# Sheet1.net
KiCad netlist of a schematic drawn in Altium Designer
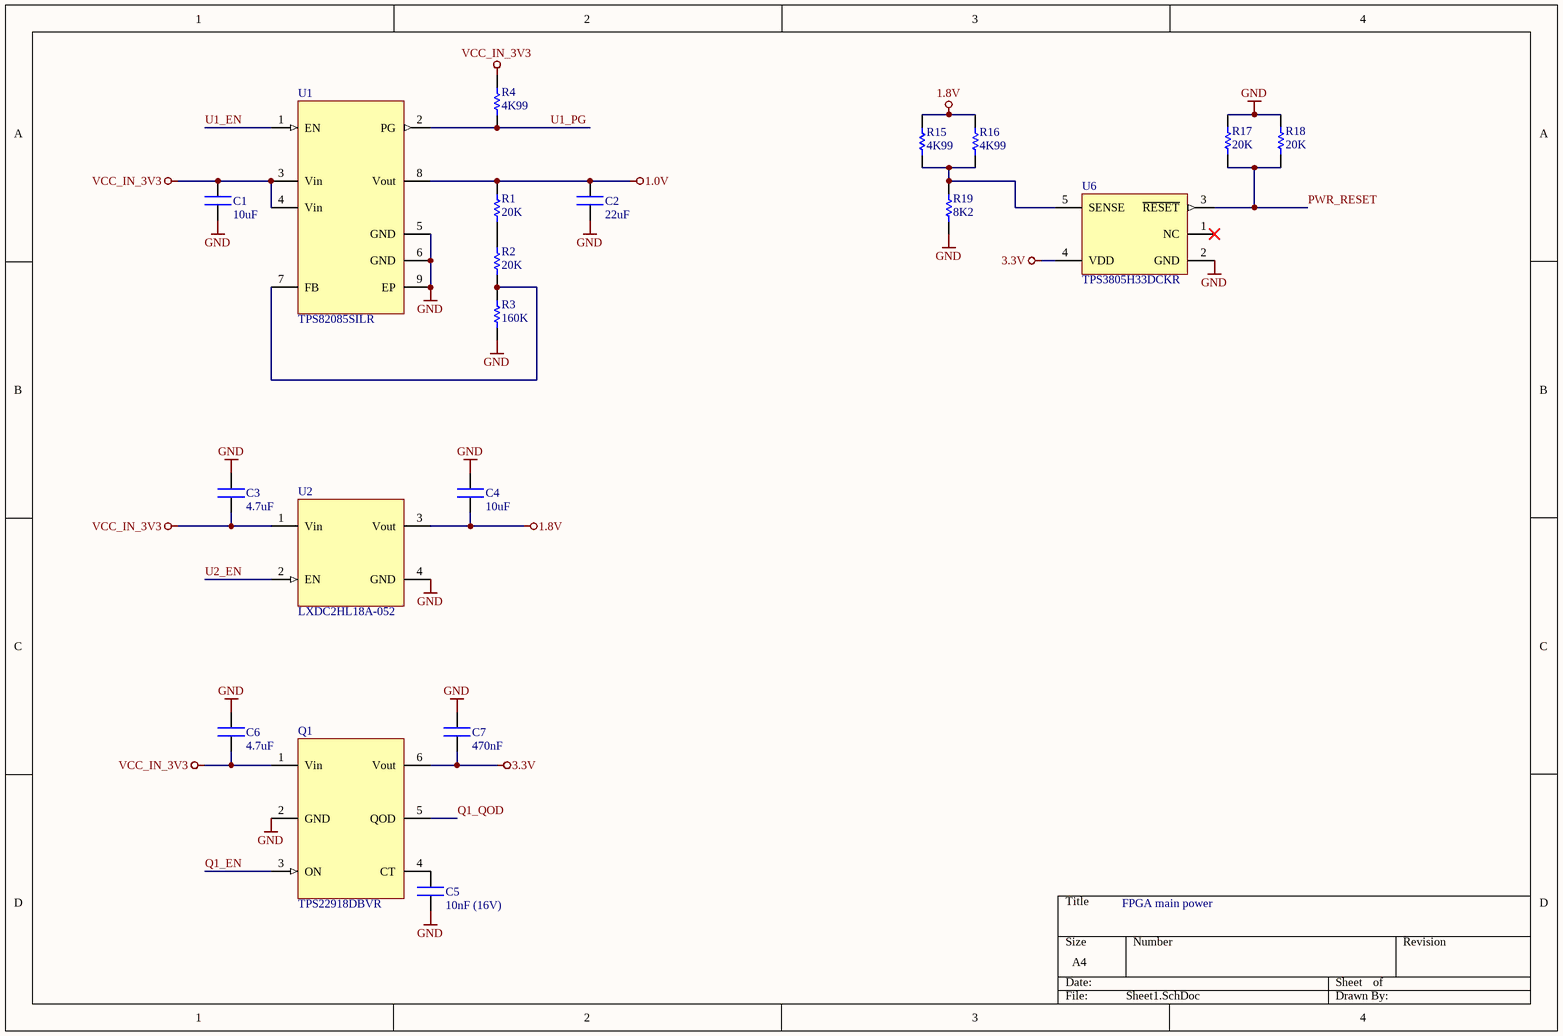
[diagram p0: Sheet1.SchDoc]

(export (version "E")
  (design (tool "Eeschema 10.0.6"))
  (components
    (comp (ref "C1")
      (value "10uF")
      (footprint "CAPC1608X08N")
      (description "Ceramic Chip Capacitor")
      (libsource (lib "Integrated_Library") (part "C0603"))
    )
    (comp (ref "C2")
      (value "22uF")
      (footprint "CAPC1608X08N")
      (description "Ceramic Chip Capacitor")
      (libsource (lib "Integrated_Library") (part "C0603"))
    )
    (comp (ref "C3")
      (value "4.7uF")
      (footprint "CAPC1005X05N")
      (description "Ceramic Chip Capacitor")
      (libsource (lib "Integrated_Library") (part "C0402"))
    )
    (comp (ref "C4")
      (value "10uF")
      (footprint "CAPC1608X08N")
      (description "Ceramic Chip Capacitor")
      (libsource (lib "Integrated_Library") (part "C0603"))
    )
    (comp (ref "C5")
      (value "10nF (16V)")
      (footprint "CAPC1005X05N")
      (description "Ceramic Chip Capacitor")
      (libsource (lib "Integrated_Library") (part "C0402"))
    )
    (comp (ref "C6")
      (value "4.7uF")
      (footprint "CAPC1005X05N")
      (description "Ceramic Chip Capacitor")
      (libsource (lib "Integrated_Library") (part "C0402"))
    )
    (comp (ref "C7")
      (value "470nF")
      (footprint "CAPC1005X05N")
      (description "Ceramic Chip Capacitor")
      (libsource (lib "Integrated_Library") (part "C0402"))
    )
    (comp (ref "Q1")
      (value "TPS22918DBVR")
      (footprint "TPS22918DBVR")
      (description "5.5-V, 2-A, 52-mΩ On-Resistance Load Switch")
      (libsource (lib "Integrated_Library") (part "TPS22918DBVR"))
    )
    (comp (ref "R1")
      (value "20K")
      (footprint "RESC1005X05N")
      (description "Ceramic Chip Resistor")
      (libsource (lib "Integrated_Library") (part "R0402"))
    )
    (comp (ref "R2")
      (value "20K")
      (footprint "RESC1005X05N")
      (description "Ceramic Chip Resistor")
      (libsource (lib "Integrated_Library") (part "R0402"))
    )
    (comp (ref "R3")
      (value "160K")
      (footprint "RESC1005X05N")
      (description "Ceramic Chip Resistor")
      (libsource (lib "Integrated_Library") (part "R0402"))
    )
    (comp (ref "R4")
      (value "4K99")
      (footprint "RESC1005X05N")
      (description "Ceramic Chip Resistor")
      (libsource (lib "Integrated_Library") (part "R0402"))
    )
    (comp (ref "R15")
      (value "4K99")
      (footprint "RESC1005X05N")
      (description "Ceramic Chip Resistor")
      (libsource (lib "Integrated_Library") (part "R0402"))
    )
    (comp (ref "R16")
      (value "4K99")
      (footprint "RESC1005X05N")
      (description "Ceramic Chip Resistor")
      (libsource (lib "Integrated_Library") (part "R0402"))
    )
    (comp (ref "R17")
      (value "20K")
      (footprint "RESC1005X05N")
      (description "Ceramic Chip Resistor")
      (libsource (lib "Integrated_Library") (part "R0402"))
    )
    (comp (ref "R18")
      (value "20K")
      (footprint "RESC1005X05N")
      (description "Ceramic Chip Resistor")
      (libsource (lib "Integrated_Library") (part "R0402"))
    )
    (comp (ref "R19")
      (value "8K2")
      (footprint "RESC1005X05N")
      (description "Ceramic Chip Resistor")
      (libsource (lib "Integrated_Library") (part "R0402"))
    )
    (comp (ref "U1")
      (value "TPS82085SILR")
      (footprint "TPS82085SILR")
      (description "3-A High Efficiency Step-Down Converter")
      (libsource (lib "Integrated_Library") (part "TPS82085SILR"))
    )
    (comp (ref "U2")
      (value "LXDC2HL18A-052")
      (footprint "LXDC2HL18A-052")
      (description "Low power step-down DC-DC converter.")
      (libsource (lib "Integrated_Library") (part "LXDC2HL18A-052"))
    )
    (comp (ref "U6")
      (value "TPS3805H33DCKR")
      (footprint "TPS3805H33DCKR")
      (fields (field (name "MANUFACTURER") "Texas Instruments"))
      (libsource (lib "Integrated_Library") (part "TPS3805H33DCKR"))
    )
  )
  (nets
    (net (code "1") (name "/PWR_RESET") (class "Default")
      (node (ref "R17") (pin "2") (pinfunction "2_2") (pintype "passive"))
      (node (ref "R18") (pin "2") (pinfunction "2_2") (pintype "passive"))
      (node (ref "U6") (pin "3") (pinfunction "~{RESET}_3") (pintype "output"))
    )
    (net (code "2") (name "/Q1_EN") (class "Default")
      (node (ref "Q1") (pin "3") (pinfunction "ON_3") (pintype "input"))
    )
    (net (code "3") (name "/Q1_QOD") (class "Default")
      (node (ref "Q1") (pin "5") (pinfunction "QOD_5") (pintype "power_in"))
    )
    (net (code "4") (name "/U1_EN") (class "Default")
      (node (ref "U1") (pin "1") (pinfunction "EN_1") (pintype "input"))
    )
    (net (code "5") (name "/U1_PG") (class "Default")
      (node (ref "R4") (pin "1") (pinfunction "1_1") (pintype "passive"))
      (node (ref "U1") (pin "2") (pinfunction "PG_2") (pintype "output"))
    )
    (net (code "6") (name "/U2_EN") (class "Default")
      (node (ref "U2") (pin "2") (pinfunction "EN_2") (pintype "input"))
    )
    (net (code "7") (name "1.0V") (class "Default")
      (node (ref "C2") (pin "2") (pinfunction "2_2") (pintype "passive"))
      (node (ref "R1") (pin "2") (pinfunction "2_2") (pintype "passive"))
      (node (ref "U1") (pin "8") (pinfunction "Vout_8") (pintype "power_in"))
    )
    (net (code "8") (name "1.8V") (class "Default")
      (node (ref "C4") (pin "2") (pinfunction "2_2") (pintype "passive"))
      (node (ref "R15") (pin "2") (pinfunction "2_2") (pintype "passive"))
      (node (ref "R16") (pin "2") (pinfunction "2_2") (pintype "passive"))
      (node (ref "U2") (pin "3") (pinfunction "Vout_3") (pintype "power_in"))
    )
    (net (code "9") (name "3.3V") (class "Default")
      (node (ref "C7") (pin "2") (pinfunction "2_2") (pintype "passive"))
      (node (ref "Q1") (pin "6") (pinfunction "Vout_6") (pintype "power_in"))
      (node (ref "U6") (pin "4") (pinfunction "VDD_4") (pintype "power_in"))
    )
    (net (code "10") (name "GND") (class "Default")
      (node (ref "C1") (pin "1") (pinfunction "1_1") (pintype "passive"))
      (node (ref "C2") (pin "1") (pinfunction "1_1") (pintype "passive"))
      (node (ref "C3") (pin "1") (pinfunction "1_1") (pintype "passive"))
      (node (ref "C4") (pin "1") (pinfunction "1_1") (pintype "passive"))
      (node (ref "C5") (pin "1") (pinfunction "1_1") (pintype "passive"))
      (node (ref "C6") (pin "1") (pinfunction "1_1") (pintype "passive"))
      (node (ref "C7") (pin "1") (pinfunction "1_1") (pintype "passive"))
      (node (ref "Q1") (pin "2") (pinfunction "GND_2") (pintype "power_in"))
      (node (ref "R17") (pin "1") (pinfunction "1_1") (pintype "passive"))
      (node (ref "R18") (pin "1") (pinfunction "1_1") (pintype "passive"))
      (node (ref "R19") (pin "1") (pinfunction "1_1") (pintype "passive"))
      (node (ref "R3") (pin "1") (pinfunction "1_1") (pintype "passive"))
      (node (ref "U1") (pin "5") (pinfunction "GND_5") (pintype "power_in"))
      (node (ref "U1") (pin "6") (pinfunction "GND_6") (pintype "power_in"))
      (node (ref "U1") (pin "9") (pinfunction "EP_9") (pintype "power_in"))
      (node (ref "U2") (pin "4") (pinfunction "GND_4") (pintype "power_in"))
      (node (ref "U6") (pin "2") (pinfunction "GND_2") (pintype "power_in"))
    )
    (net (code "11") (name "Net-(Q1-CT)") (class "Default")
      (node (ref "C5") (pin "2") (pinfunction "2_2") (pintype "passive"))
      (node (ref "Q1") (pin "4") (pinfunction "CT_4") (pintype "power_in"))
    )
    (net (code "12") (name "Net-(R1-Pad1)") (class "Default")
      (node (ref "R1") (pin "1") (pinfunction "1_1") (pintype "passive"))
      (node (ref "R2") (pin "2") (pinfunction "2_2") (pintype "passive"))
    )
    (net (code "13") (name "Net-(U1-FB)") (class "Default")
      (node (ref "R2") (pin "1") (pinfunction "1_1") (pintype "passive"))
      (node (ref "R3") (pin "2") (pinfunction "2_2") (pintype "passive"))
      (node (ref "U1") (pin "7") (pinfunction "FB_7") (pintype "passive"))
    )
    (net (code "14") (name "Net-(U6-SENSE)") (class "Default")
      (node (ref "R15") (pin "1") (pinfunction "1_1") (pintype "passive"))
      (node (ref "R16") (pin "1") (pinfunction "1_1") (pintype "passive"))
      (node (ref "R19") (pin "2") (pinfunction "2_2") (pintype "passive"))
      (node (ref "U6") (pin "5") (pinfunction "SENSE_5") (pintype "passive"))
    )
    (net (code "15") (name "VCC_IN_3V3") (class "Default")
      (node (ref "C1") (pin "2") (pinfunction "2_2") (pintype "passive"))
      (node (ref "C3") (pin "2") (pinfunction "2_2") (pintype "passive"))
      (node (ref "C6") (pin "2") (pinfunction "2_2") (pintype "passive"))
      (node (ref "Q1") (pin "1") (pinfunction "Vin_1") (pintype "power_in"))
      (node (ref "R4") (pin "2") (pinfunction "2_2") (pintype "passive"))
      (node (ref "U1") (pin "3") (pinfunction "Vin_3") (pintype "power_in"))
      (node (ref "U1") (pin "4") (pinfunction "Vin_4") (pintype "power_in"))
      (node (ref "U2") (pin "1") (pinfunction "Vin_1") (pintype "power_in"))
    )
    (net (code "16") (name "unconnected-(U6-NC-Pad1)") (class "Default")
      (node (ref "U6") (pin "1") (pinfunction "NC_1") (pintype "passive+no_connect"))
    )
  )
)
